# P2D-001.net
KiCad netlist of a schematic drawn in EAGLE
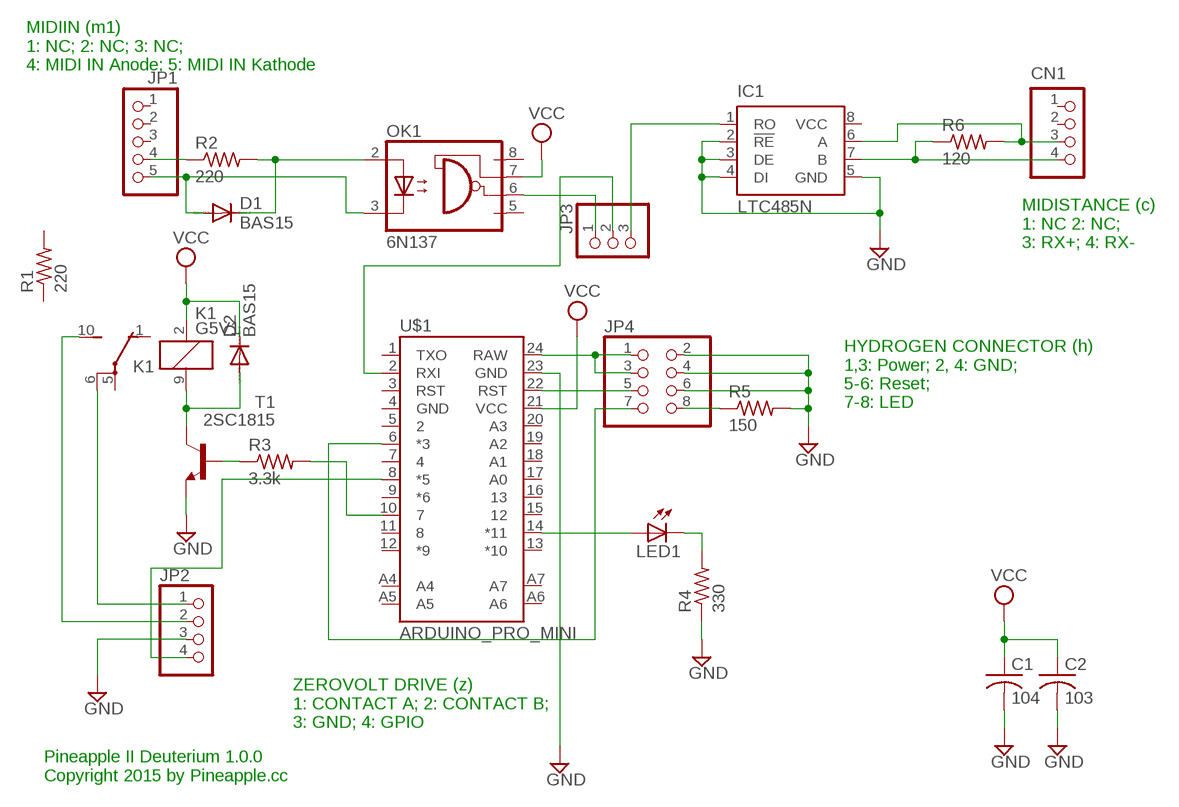
[diagram p0: schematic, sheet 1]

(export (version "E")
  (design (tool "Eeschema 10.0.6"))
  (components
    (comp (ref "C1")
      (value "104")
      (footprint "eagle-import:C025-025X050")
      (libsource (lib "eagle-import") (part "C-US025-025X050"))
    )
    (comp (ref "C2")
      (value "103")
      (footprint "eagle-import:C025-025X050")
      (libsource (lib "eagle-import") (part "C-US025-025X050"))
    )
    (comp (ref "CN1")
      (value "B4B-PH-K-S")
      (footprint "eagle-import:B4B-PH-K-S")
      (libsource (lib "eagle-import") (part "B4B-PH-K-S"))
    )
    (comp (ref "D1")
      (value "BAS15")
      (footprint "eagle-import:DO34-7")
      (libsource (lib "eagle-import") (part "BAS15"))
    )
    (comp (ref "D2")
      (value "BAS15")
      (footprint "eagle-import:DO34-7")
      (libsource (lib "eagle-import") (part "BAS15"))
    )
    (comp (ref "IC1")
      (value "LTC485N")
      (footprint "eagle-import:DIL08")
      (libsource (lib "eagle-import") (part "LTC485N"))
    )
    (comp (ref "JP1")
      (value "PINHD-1X5")
      (footprint "eagle-import:1X05")
      (libsource (lib "eagle-import") (part "PINHD-1X5"))
    )
    (comp (ref "JP2")
      (value "PINHD-1X4")
      (footprint "eagle-import:1X04")
      (libsource (lib "eagle-import") (part "PINHD-1X4"))
    )
    (comp (ref "JP3")
      (value "PINHD-1X3")
      (footprint "eagle-import:1X03")
      (libsource (lib "eagle-import") (part "PINHD-1X3"))
    )
    (comp (ref "JP4")
      (value "PINHD-2X4")
      (footprint "eagle-import:2X04")
      (libsource (lib "eagle-import") (part "PINHD-2X4"))
    )
    (comp (ref "K1")
      (value "G5V1")
      (footprint "eagle-import:G5V1")
      (fields (field (name "MPN") "G5V-1-DC24"))
      (libsource (lib "eagle-import") (part "G5V1"))
    )
    (comp (ref "LED1")
      (value "LED3MM")
      (footprint "eagle-import:LED3MM")
      (libsource (lib "eagle-import") (part "LED3MM"))
    )
    (comp (ref "OK1")
      (value "6N137")
      (footprint "eagle-import:DIL08")
      (libsource (lib "eagle-import") (part "6N137"))
    )
    (comp (ref "R1")
      (value "220")
      (footprint "eagle-import:0204_5")
      (libsource (lib "eagle-import") (part "R-US_0204/5"))
    )
    (comp (ref "R2")
      (value "220")
      (footprint "eagle-import:0204_5")
      (libsource (lib "eagle-import") (part "R-US_0204/5"))
    )
    (comp (ref "R3")
      (value "3.3k")
      (footprint "eagle-import:0204_5")
      (libsource (lib "eagle-import") (part "R-US_0204/5"))
    )
    (comp (ref "R4")
      (value "330")
      (footprint "eagle-import:0204_5")
      (libsource (lib "eagle-import") (part "R-US_0204/5"))
    )
    (comp (ref "R5")
      (value "150")
      (footprint "eagle-import:0204_5")
      (libsource (lib "eagle-import") (part "R-US_0204/5"))
    )
    (comp (ref "R6")
      (value "120")
      (footprint "eagle-import:0204_5")
      (libsource (lib "eagle-import") (part "R-US_0204/5"))
    )
    (comp (ref "T1")
      (value "2SC1815")
      (footprint "eagle-import:TO92-ECB")
      (libsource (lib "eagle-import") (part "2SC1815"))
    )
    (comp (ref "U$1")
      (value "ARDUINO_PRO_MINI")
      (footprint "eagle-import:ARDUINO_PRO_MINI")
      (libsource (lib "eagle-import") (part "ARDUINO_PRO_MINI"))
    )
  )
  (nets
    (net (code "1") (name "GND") (class "Default")
      (node (ref "C1") (pin "2") (pinfunction "2_2") (pintype "passive"))
      (node (ref "C2") (pin "2") (pinfunction "2_2") (pintype "passive"))
      (node (ref "IC1") (pin "2") (pinfunction "~{RE}_2") (pintype "input"))
      (node (ref "IC1") (pin "3") (pinfunction "DE_3") (pintype "input"))
      (node (ref "IC1") (pin "4") (pinfunction "DI_4") (pintype "input"))
      (node (ref "IC1") (pin "5") (pinfunction "GND_5") (pintype "input"))
      (node (ref "JP2") (pin "3") (pinfunction "3_3") (pintype "passive"))
      (node (ref "JP4") (pin "2") (pinfunction "2_2") (pintype "passive"))
      (node (ref "JP4") (pin "4") (pinfunction "4_4") (pintype "passive"))
      (node (ref "JP4") (pin "6") (pinfunction "6_6") (pintype "passive"))
      (node (ref "R4") (pin "1") (pinfunction "1_1") (pintype "passive"))
      (node (ref "R5") (pin "2") (pinfunction "2_2") (pintype "passive"))
      (node (ref "T1") (pin "E") (pinfunction "E_E") (pintype "passive"))
      (node (ref "U$1") (pin "23") (pinfunction "GND_23") (pintype "bidirectional"))
    )
    (net (code "2") (name "Net-(IC1-A)") (class "Default")
      (node (ref "CN1") (pin "3") (pinfunction "3_3") (pintype "passive"))
      (node (ref "IC1") (pin "6") (pinfunction "A_6") (pintype "bidirectional"))
      (node (ref "R6") (pin "2") (pinfunction "2_2") (pintype "passive"))
    )
    (net (code "3") (name "Net-(IC1-B)") (class "Default")
      (node (ref "CN1") (pin "4") (pinfunction "4_4") (pintype "passive"))
      (node (ref "IC1") (pin "7") (pinfunction "B_7") (pintype "bidirectional"))
      (node (ref "R6") (pin "1") (pinfunction "1_1") (pintype "passive"))
    )
    (net (code "4") (name "Net-(IC1-RO)") (class "Default")
      (node (ref "IC1") (pin "1") (pinfunction "RO_1") (pintype "output"))
      (node (ref "JP3") (pin "3") (pinfunction "3_3") (pintype "passive"))
    )
    (net (code "5") (name "Net-(JP1-Pad4)") (class "Default")
      (node (ref "JP1") (pin "4") (pinfunction "4_4") (pintype "passive"))
      (node (ref "R2") (pin "1") (pinfunction "1_1") (pintype "passive"))
    )
    (net (code "6") (name "Net-(JP2-Pad1)") (class "Default")
      (node (ref "JP2") (pin "1") (pinfunction "1_1") (pintype "passive"))
      (node (ref "K1") (pin "6") (pinfunction "P_6") (pintype "passive"))
    )
    (net (code "7") (name "Net-(JP4-Pad5)") (class "Default")
      (node (ref "JP4") (pin "5") (pinfunction "5_5") (pintype "passive"))
      (node (ref "U$1") (pin "22") (pinfunction "RST_22") (pintype "bidirectional"))
    )
    (net (code "8") (name "Net-(JP4-Pad8)") (class "Default")
      (node (ref "JP4") (pin "8") (pinfunction "8_8") (pintype "passive"))
      (node (ref "R5") (pin "1") (pinfunction "1_1") (pintype "passive"))
    )
    (net (code "9") (name "Net-(K1A-2)") (class "Default")
      (node (ref "D2") (pin "A") (pinfunction "A_A") (pintype "passive"))
      (node (ref "K1") (pin "9") (pinfunction "2_9") (pintype "passive"))
      (node (ref "T1") (pin "C") (pinfunction "C_C") (pintype "passive"))
    )
    (net (code "10") (name "Net-(K1B-S)") (class "Default")
      (node (ref "JP2") (pin "2") (pinfunction "2_2") (pintype "passive"))
      (node (ref "K1") (pin "10") (pinfunction "S_10") (pintype "passive"))
    )
    (net (code "11") (name "Net-(LED1-C)") (class "Default")
      (node (ref "LED1") (pin "K") (pinfunction "C_K") (pintype "passive"))
      (node (ref "R4") (pin "2") (pinfunction "2_2") (pintype "passive"))
    )
    (net (code "12") (name "Net-(OK1-A)") (class "Default")
      (node (ref "D1") (pin "C") (pinfunction "C_C") (pintype "passive"))
      (node (ref "OK1") (pin "2") (pinfunction "A_2") (pintype "passive"))
      (node (ref "R2") (pin "2") (pinfunction "2_2") (pintype "passive"))
    )
    (net (code "13") (name "Net-(OK1-C)") (class "Default")
      (node (ref "D1") (pin "A") (pinfunction "A_A") (pintype "passive"))
      (node (ref "JP1") (pin "5") (pinfunction "5_5") (pintype "passive"))
      (node (ref "OK1") (pin "3") (pinfunction "C_3") (pintype "passive"))
    )
    (net (code "14") (name "Net-(OK1-VO)") (class "Default")
      (node (ref "JP3") (pin "1") (pinfunction "1_1") (pintype "passive"))
      (node (ref "OK1") (pin "6") (pinfunction "VO_6") (pintype "passive"))
    )
    (net (code "15") (name "Net-(R3-Pad1)") (class "Default")
      (node (ref "R3") (pin "1") (pinfunction "1_1") (pintype "passive"))
      (node (ref "T1") (pin "B") (pinfunction "B_B") (pintype "passive"))
    )
    (net (code "16") (name "Net-(U$1-*3)") (class "Default")
      (node (ref "JP4") (pin "7") (pinfunction "7_7") (pintype "passive"))
      (node (ref "U$1") (pin "6") (pinfunction "*3_6") (pintype "bidirectional"))
    )
    (net (code "17") (name "Net-(U$1-*5)") (class "Default")
      (node (ref "JP2") (pin "4") (pinfunction "4_4") (pintype "passive"))
      (node (ref "U$1") (pin "8") (pinfunction "*5_8") (pintype "bidirectional"))
    )
    (net (code "18") (name "Net-(U$1-*11)") (class "Default")
      (node (ref "LED1") (pin "A") (pinfunction "A_A") (pintype "passive"))
      (node (ref "U$1") (pin "14") (pinfunction "*11_14") (pintype "bidirectional"))
    )
    (net (code "19") (name "Net-(U$1-7)") (class "Default")
      (node (ref "R3") (pin "2") (pinfunction "2_2") (pintype "passive"))
      (node (ref "U$1") (pin "10") (pinfunction "7_10") (pintype "bidirectional"))
    )
    (net (code "20") (name "Net-(U$1-RAW)") (class "Default")
      (node (ref "JP4") (pin "1") (pinfunction "1_1") (pintype "passive"))
      (node (ref "JP4") (pin "3") (pinfunction "3_3") (pintype "passive"))
      (node (ref "U$1") (pin "24") (pinfunction "RAW_24") (pintype "bidirectional"))
    )
    (net (code "21") (name "Net-(U$1-RXI)") (class "Default")
      (node (ref "JP3") (pin "2") (pinfunction "2_2") (pintype "passive"))
      (node (ref "U$1") (pin "2") (pinfunction "RXI_2") (pintype "bidirectional"))
    )
    (net (code "22") (name "VCC") (class "Default")
      (node (ref "C1") (pin "1") (pinfunction "1_1") (pintype "passive"))
      (node (ref "C2") (pin "1") (pinfunction "1_1") (pintype "passive"))
      (node (ref "D2") (pin "C") (pinfunction "C_C") (pintype "passive"))
      (node (ref "K1") (pin "2") (pinfunction "1_2") (pintype "passive"))
      (node (ref "OK1") (pin "7") (pinfunction "VE_7") (pintype "passive"))
      (node (ref "U$1") (pin "21") (pinfunction "VCC_21") (pintype "bidirectional"))
    )
    (net (code "23") (name "unconnected-(CN1-Pad1)") (class "Default")
      (node (ref "CN1") (pin "1") (pinfunction "1_1") (pintype "passive"))
    )
    (net (code "24") (name "unconnected-(CN1-Pad2)") (class "Default")
      (node (ref "CN1") (pin "2") (pinfunction "2_2") (pintype "passive"))
    )
    (net (code "25") (name "unconnected-(IC1-VCC-Pad8)") (class "Default")
      (node (ref "IC1") (pin "8") (pinfunction "VCC_8") (pintype "input"))
    )
    (net (code "26") (name "unconnected-(JP1-Pad1)") (class "Default")
      (node (ref "JP1") (pin "1") (pinfunction "1_1") (pintype "passive"))
    )
    (net (code "27") (name "unconnected-(JP1-Pad2)") (class "Default")
      (node (ref "JP1") (pin "2") (pinfunction "2_2") (pintype "passive"))
    )
    (net (code "28") (name "unconnected-(JP1-Pad3)") (class "Default")
      (node (ref "JP1") (pin "3") (pinfunction "3_3") (pintype "passive"))
    )
    (net (code "29") (name "unconnected-(K1B-O-Pad1)") (class "Default")
      (node (ref "K1") (pin "1") (pinfunction "O_1") (pintype "passive"))
    )
    (net (code "30") (name "unconnected-(K1B-P-Pad5)") (class "Default")
      (node (ref "K1") (pin "5") (pinfunction "P_5") (pintype "passive"))
    )
    (net (code "31") (name "unconnected-(OK1-GND-Pad5)") (class "Default")
      (node (ref "OK1") (pin "5") (pinfunction "GND_5") (pintype "passive"))
    )
    (net (code "32") (name "unconnected-(OK1-VCC-Pad8)") (class "Default")
      (node (ref "OK1") (pin "8") (pinfunction "VCC_8") (pintype "passive"))
    )
    (net (code "33") (name "unconnected-(R1-Pad1)") (class "Default")
      (node (ref "R1") (pin "1") (pinfunction "1_1") (pintype "passive"))
    )
    (net (code "34") (name "unconnected-(R1-Pad2)") (class "Default")
      (node (ref "R1") (pin "2") (pinfunction "2_2") (pintype "passive"))
    )
    (net (code "35") (name "unconnected-(U$1-*6-Pad9)") (class "Default")
      (node (ref "U$1") (pin "9") (pinfunction "*6_9") (pintype "bidirectional"))
    )
    (net (code "36") (name "unconnected-(U$1-*9-Pad12)") (class "Default")
      (node (ref "U$1") (pin "12") (pinfunction "*9_12") (pintype "bidirectional"))
    )
    (net (code "37") (name "unconnected-(U$1-*10-Pad13)") (class "Default")
      (node (ref "U$1") (pin "13") (pinfunction "*10_13") (pintype "bidirectional"))
    )
    (net (code "38") (name "unconnected-(U$1-2-Pad5)") (class "Default")
      (node (ref "U$1") (pin "5") (pinfunction "2_5") (pintype "bidirectional"))
    )
    (net (code "39") (name "unconnected-(U$1-4-Pad7)") (class "Default")
      (node (ref "U$1") (pin "7") (pinfunction "4_7") (pintype "bidirectional"))
    )
    (net (code "40") (name "unconnected-(U$1-8-Pad11)") (class "Default")
      (node (ref "U$1") (pin "11") (pinfunction "8_11") (pintype "bidirectional"))
    )
    (net (code "41") (name "unconnected-(U$1-12-Pad15)") (class "Default")
      (node (ref "U$1") (pin "15") (pinfunction "12_15") (pintype "bidirectional"))
    )
    (net (code "42") (name "unconnected-(U$1-13-Pad16)") (class "Default")
      (node (ref "U$1") (pin "16") (pinfunction "13_16") (pintype "bidirectional"))
    )
    (net (code "43") (name "unconnected-(U$1-A0-Pad17)") (class "Default")
      (node (ref "U$1") (pin "17") (pinfunction "A0_17") (pintype "bidirectional"))
    )
    (net (code "44") (name "unconnected-(U$1-A1-Pad18)") (class "Default")
      (node (ref "U$1") (pin "18") (pinfunction "A1_18") (pintype "bidirectional"))
    )
    (net (code "45") (name "unconnected-(U$1-A2-Pad19)") (class "Default")
      (node (ref "U$1") (pin "19") (pinfunction "A2_19") (pintype "bidirectional"))
    )
    (net (code "46") (name "unconnected-(U$1-A3-Pad20)") (class "Default")
      (node (ref "U$1") (pin "20") (pinfunction "A3_20") (pintype "bidirectional"))
    )
    (net (code "47") (name "unconnected-(U$1-GND-Pad4)") (class "Default")
      (node (ref "U$1") (pin "4") (pinfunction "GND_4") (pintype "bidirectional"))
    )
    (net (code "48") (name "unconnected-(U$1-PadA4)") (class "Default")
      (node (ref "U$1") (pin "A4") (pinfunction "A4_A4") (pintype "bidirectional"))
    )
    (net (code "49") (name "unconnected-(U$1-PadA5)") (class "Default")
      (node (ref "U$1") (pin "A5") (pinfunction "A5_A5") (pintype "bidirectional"))
    )
    (net (code "50") (name "unconnected-(U$1-PadA6)") (class "Default")
      (node (ref "U$1") (pin "A6") (pinfunction "A6_A6") (pintype "bidirectional"))
    )
    (net (code "51") (name "unconnected-(U$1-PadA7)") (class "Default")
      (node (ref "U$1") (pin "A7") (pinfunction "A7_A7") (pintype "bidirectional"))
    )
    (net (code "52") (name "unconnected-(U$1-RST-Pad3)") (class "Default")
      (node (ref "U$1") (pin "3") (pinfunction "RST_3") (pintype "bidirectional"))
    )
    (net (code "53") (name "unconnected-(U$1-TXO-Pad1)") (class "Default")
      (node (ref "U$1") (pin "1") (pinfunction "TXO_1") (pintype "bidirectional"))
    )
  )
)
